# Power_IN.net
KiCad netlist of a schematic drawn in Altium Designer
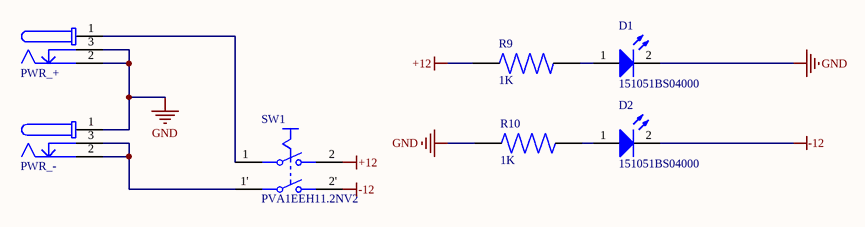
[diagram p0: Power_IN.SchDoc]

(export (version "E")
  (design (tool "Eeschema 10.0.6"))
  (components
    (comp (ref "D1")
      (value "151051BS04000")
      (footprint "WL-TMRC_D5.9H8.7")
      (libsource (lib "Altium Content Vault") (part "LED_Blue_1A-2K"))
    )
    (comp (ref "D2")
      (value "151051BS04000")
      (footprint "WL-TMRC_D5.9H8.7")
      (libsource (lib "Altium Content Vault") (part "LED_Blue_1A-2K"))
    )
    (comp (ref "PWR_+")
      (value "694106301002")
      (footprint "PCBComponent_1")
      (description "DC Power Jack Connector WR-DC, Male, Right Angled, THT, 5 A, 24 V")
      (fields (field (name "MANUFACTURER") "Wurth Elektronik"))
      (libsource (lib "Integrated_Library1") (part "694106301002"))
    )
    (comp (ref "PWR_-")
      (value "694106301002")
      (footprint "PCBComponent_1")
      (description "DC Power Jack Connector WR-DC, Male, Right Angled, THT, 5 A, 24 V")
      (fields (field (name "MANUFACTURER") "Wurth Elektronik"))
      (libsource (lib "Integrated_Library1") (part "694106301002"))
    )
    (comp (ref "R9")
      (value "1K")
      (footprint "RESAD1100W55L680D260")
      (description "1.07 kOhms Â±1% 0.25W, 1/4W Through Hole Resistor Axial - Metal Film")
      (fields (field (name "MF") "Yageo") (field (name "MP") "MFR-25FBF52-1K"))
      (libsource (lib "MFR-25FBF52-1K") (part "MFR-25FBF52-1K"))
    )
    (comp (ref "R10")
      (value "1K")
      (footprint "RESAD1100W55L680D260")
      (description "1.07 kOhms Â±1% 0.25W, 1/4W Through Hole Resistor Axial - Metal Film")
      (fields (field (name "MF") "Yageo") (field (name "MP") "MFR-25FBF52-1K"))
      (libsource (lib "MFR-25FBF52-1K") (part "MFR-25FBF52-1K"))
    )
    (comp (ref "SW1")
      (value "PVA1EEH11.2NV2")
      (footprint "FP-PVA1EEH11_2NV2-MFG")
      (description "SWITCH PUSH DPST 0.1A 32V")
      (libsource (lib "Altium Content Vault") (part "0a7b0f685d7af6e0316c3509192f32d"))
    )
  )
  (nets
    (net (code "1") (name "+12") (class "Default")
      (node (ref "R9") (pin "1") (pinfunction "1_1") (pintype "passive"))
      (node (ref "SW1") (pin "2") (pinfunction "2_2") (pintype "passive"))
    )
    (net (code "2") (name "-12") (class "Default")
      (node (ref "D2") (pin "2") (pinfunction "K_2") (pintype "passive"))
      (node (ref "SW1") (pin "2'") (pinfunction "2'_2'") (pintype "passive"))
    )
    (net (code "3") (name "GND") (class "Default")
      (node (ref "D1") (pin "2") (pinfunction "K_2") (pintype "passive"))
      (node (ref "PWR_+") (pin "2") (pinfunction "2_2") (pintype "passive"))
      (node (ref "PWR_+") (pin "3") (pinfunction "3_3") (pintype "passive"))
      (node (ref "PWR_-") (pin "1") (pinfunction "1_1") (pintype "passive"))
      (node (ref "R10") (pin "1") (pinfunction "1_1") (pintype "passive"))
    )
    (net (code "4") (name "Net-(D1-A)") (class "Default")
      (node (ref "D1") (pin "1") (pinfunction "A_1") (pintype "passive"))
      (node (ref "R9") (pin "2") (pinfunction "2_2") (pintype "passive"))
    )
    (net (code "5") (name "Net-(D2-A)") (class "Default")
      (node (ref "D2") (pin "1") (pinfunction "A_1") (pintype "passive"))
      (node (ref "R10") (pin "2") (pinfunction "2_2") (pintype "passive"))
    )
    (net (code "6") (name "Net-(PWR_+-Pad1)") (class "Default")
      (node (ref "PWR_+") (pin "1") (pinfunction "1_1") (pintype "passive"))
      (node (ref "SW1") (pin "1") (pinfunction "1_1") (pintype "passive"))
    )
    (net (code "7") (name "Net-(PWR_--Pad2)") (class "Default")
      (node (ref "PWR_-") (pin "2") (pinfunction "2_2") (pintype "passive"))
      (node (ref "PWR_-") (pin "3") (pinfunction "3_3") (pintype "passive"))
      (node (ref "SW1") (pin "1'") (pinfunction "1'_1'") (pintype "passive"))
    )
  )
)
